# PM12_CFD_Main.net
KiCad netlist of a schematic drawn in Altium Designer
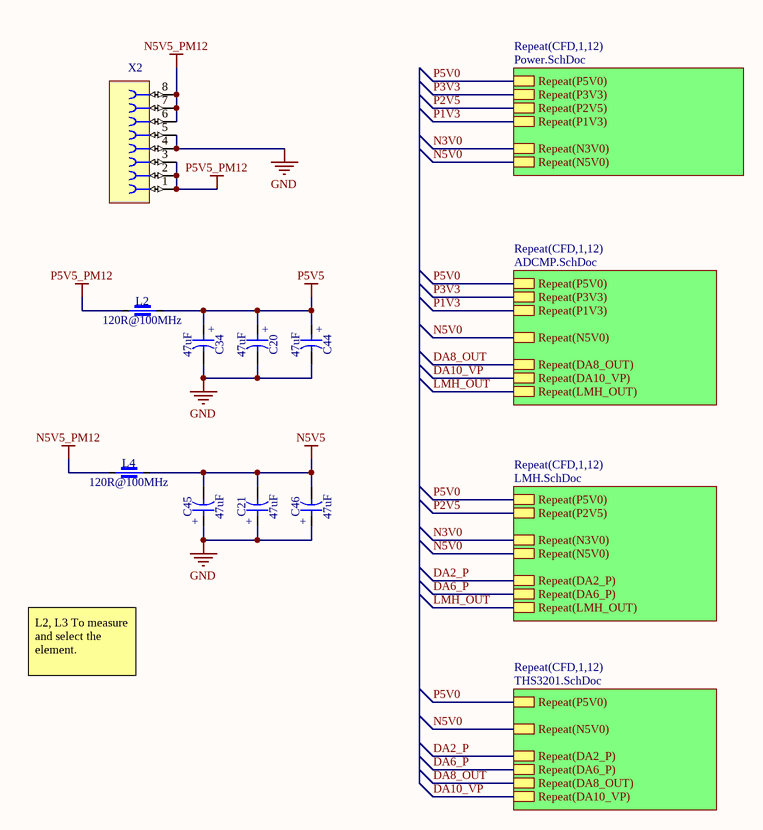
[diagram p0: PM12_CFD_Main.SchDoc]

(export (version "E")
  (design (tool "Eeschema 10.0.6"))
  (components
    (comp (ref "C20")
      (value "47uF")
      (footprint "CAPAE530X610N")
      (description "Polarised capacitor")
      (fields
        (field (name "PART NUMBER") "CAE530-610_47UF_16V_20%")
        (field (name "VOLTAGE") "16V")
        (field (name "AUTHOR") "CERN DEM HF")
      )
      (libsource (lib "Capacitors") (part "Capacitor - polarized"))
    )
    (comp (ref "C21")
      (value "47uF")
      (footprint "CAPAE530X610N")
      (description "Polarised capacitor")
      (fields
        (field (name "PART NUMBER") "CAE530-610_47UF_16V_20%")
        (field (name "VOLTAGE") "16V")
        (field (name "AUTHOR") "CERN DEM HF")
      )
      (libsource (lib "Capacitors") (part "Capacitor - polarized"))
    )
    (comp (ref "C34")
      (value "47uF")
      (footprint "CAPAE530X610N")
      (description "Polarised capacitor")
      (fields
        (field (name "PART NUMBER") "CAE530-610_47UF_16V_20%")
        (field (name "VOLTAGE") "16V")
        (field (name "AUTHOR") "CERN DEM HF")
      )
      (libsource (lib "Capacitors") (part "Capacitor - polarized"))
    )
    (comp (ref "C44")
      (value "47uF")
      (footprint "CAPAE530X610N")
      (description "Polarised capacitor")
      (fields
        (field (name "PART NUMBER") "CAE530-610_47UF_16V_20%")
        (field (name "VOLTAGE") "16V")
        (field (name "AUTHOR") "CERN DEM HF")
      )
      (libsource (lib "Capacitors") (part "Capacitor - polarized"))
    )
    (comp (ref "C45")
      (value "47uF")
      (footprint "CAPAE530X610N")
      (description "Polarised capacitor")
      (fields
        (field (name "PART NUMBER") "CAE530-610_47UF_16V_20%")
        (field (name "VOLTAGE") "16V")
        (field (name "AUTHOR") "CERN DEM HF")
      )
      (libsource (lib "Capacitors") (part "Capacitor - polarized"))
    )
    (comp (ref "C46")
      (value "47uF")
      (footprint "CAPAE530X610N")
      (description "Polarised capacitor")
      (fields
        (field (name "PART NUMBER") "CAE530-610_47UF_16V_20%")
        (field (name "VOLTAGE") "16V")
        (field (name "AUTHOR") "CERN DEM HF")
      )
      (libsource (lib "Capacitors") (part "Capacitor - polarized"))
    )
    (comp (ref "L2")
      (value "120R@100MHz")
      (footprint "IND_MURATA_BLM31KN")
      (fields
        (field (name "PART NUMBER") "IND1206_MURATA_BLM31KN121SN1")
        (field (name "POWER") "6A")
        (field (name "TOLERANCE") "±25%")
        (field (name "AUTHOR") "CERN DEM HF")
      )
      (libsource (lib "Inductors & Transformers") (part "Ferrite Bead"))
    )
    (comp (ref "L4")
      (value "120R@100MHz")
      (footprint "IND_MURATA_BLM31KN")
      (fields
        (field (name "PART NUMBER") "IND1206_MURATA_BLM31KN121SN1")
        (field (name "POWER") "6A")
        (field (name "TOLERANCE") "±25%")
        (field (name "AUTHOR") "CERN DEM HF")
      )
      (libsource (lib "Inductors & Transformers") (part "Ferrite Bead"))
    )
    (comp (ref "X2")
      (value "Socket 8")
      (footprint "SAMTEC_CES-108-01-T-S")
      (description "Connector 8 Female")
      (fields
        (field (name "PART NUMBER") "SAMTEC_CES-108-01-L-S")
        (field (name "MANUFACTURER") "SAMTEC")
        (field (name "AUTHOR") "CERN DEM HF")
      )
      (libsource (lib "Connectors") (part "Connector 8 Female"))
    )
  )
  (nets
    (net (code "12") (name "GND") (class "Default")
      (node (ref "C20") (pin "2") (pinfunction "2_2") (pintype "passive"))
      (node (ref "C21") (pin "1") (pinfunction "1_1") (pintype "passive"))
      (node (ref "C34") (pin "2") (pinfunction "2_2") (pintype "passive"))
      (node (ref "C44") (pin "2") (pinfunction "2_2") (pintype "passive"))
      (node (ref "C45") (pin "1") (pinfunction "1_1") (pintype "passive"))
      (node (ref "C46") (pin "1") (pinfunction "1_1") (pintype "passive"))
      (node (ref "X2") (pin "4") (pinfunction "4_4") (pintype "bidirectional"))
      (node (ref "X2") (pin "5") (pinfunction "5_5") (pintype "bidirectional"))
    )
    (net (code "13") (name "N5V5") (class "Default")
      (node (ref "C21") (pin "2") (pinfunction "2_2") (pintype "passive"))
      (node (ref "C45") (pin "2") (pinfunction "2_2") (pintype "passive"))
      (node (ref "C46") (pin "2") (pinfunction "2_2") (pintype "passive"))
      (node (ref "L4") (pin "2") (pinfunction "2_2") (pintype "passive"))
    )
    (net (code "14") (name "N5V5_PM12") (class "Default")
      (node (ref "L4") (pin "1") (pinfunction "1_1") (pintype "passive"))
      (node (ref "X2") (pin "6") (pinfunction "6_6") (pintype "bidirectional"))
      (node (ref "X2") (pin "7") (pinfunction "7_7") (pintype "bidirectional"))
      (node (ref "X2") (pin "8") (pinfunction "8_8") (pintype "bidirectional"))
    )
    (net (code "15") (name "P5V5") (class "Default")
      (node (ref "C20") (pin "1") (pinfunction "1_1") (pintype "passive"))
      (node (ref "C34") (pin "1") (pinfunction "1_1") (pintype "passive"))
      (node (ref "C44") (pin "1") (pinfunction "1_1") (pintype "passive"))
      (node (ref "L2") (pin "2") (pinfunction "2_2") (pintype "passive"))
    )
    (net (code "16") (name "P5V5_PM12") (class "Default")
      (node (ref "L2") (pin "1") (pinfunction "1_1") (pintype "passive"))
      (node (ref "X2") (pin "1") (pinfunction "1_1") (pintype "bidirectional"))
      (node (ref "X2") (pin "2") (pinfunction "2_2") (pintype "bidirectional"))
      (node (ref "X2") (pin "3") (pinfunction "3_3") (pintype "bidirectional"))
    )
  )
)
